# QFN32-TQFP32_v1_0.net
KiCad netlist of a schematic drawn in EAGLE
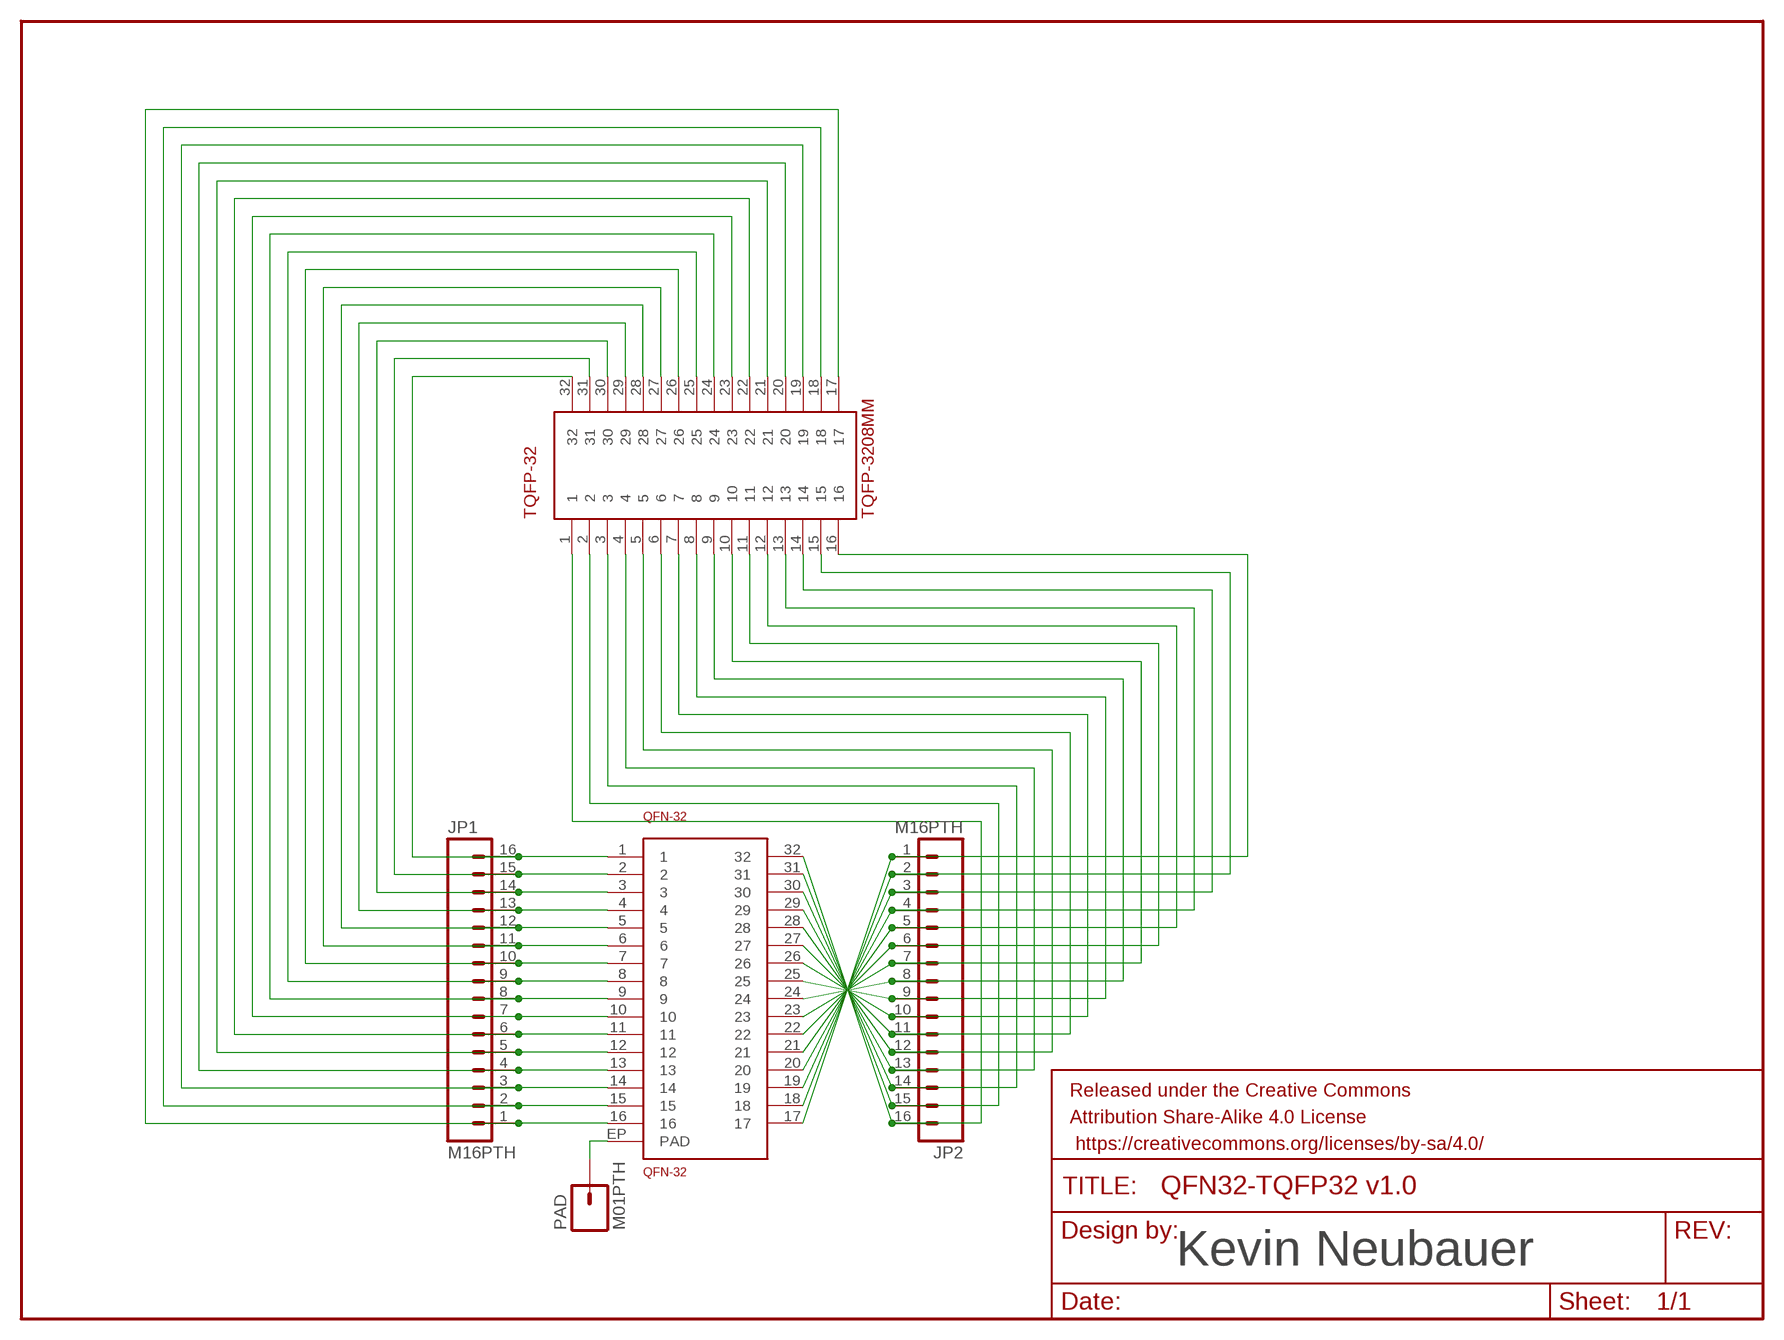
[diagram p0: schematic, sheet 1]

(export (version "E")
  (design (tool "Eeschema 10.0.6"))
  (components
    (comp (ref "FRAME1")
      (value "FRAME-LETTER")
      (footprint "eagle-import:CREATIVE_COMMONS")
      (libsource (lib "eagle-import") (part "FRAME-LETTER"))
    )
    (comp (ref "JP1")
      (value "M16PTH")
      (footprint "eagle-import:1X16")
      (libsource (lib "eagle-import") (part "M16PTH"))
    )
    (comp (ref "JP2")
      (value "M16PTH")
      (footprint "eagle-import:1X16")
      (libsource (lib "eagle-import") (part "M16PTH"))
    )
    (comp (ref "PAD")
      (value "M01PTH")
      (footprint "eagle-import:1X01")
      (libsource (lib "eagle-import") (part "M01PTH"))
    )
    (comp (ref "QFN-32")
      (value "QFN-32")
      (footprint "eagle-import:QFN-32")
      (libsource (lib "eagle-import") (part "QFN-32"))
    )
    (comp (ref "TQFP-32")
      (value "TQFP-3208MM")
      (footprint "eagle-import:TQFP32-08")
      (libsource (lib "eagle-import") (part "TQFP-3208MM"))
    )
  )
  (nets
    (net (code "1") (name "Net-(JP1-Pad1)") (class "Default")
      (node (ref "JP1") (pin "1") (pinfunction "1_1") (pintype "passive"))
      (node (ref "QFN-32") (pin "16") (pinfunction "16_16") (pintype "bidirectional"))
      (node (ref "TQFP-32") (pin "17") (pinfunction "17_17") (pintype "bidirectional"))
    )
    (net (code "2") (name "Net-(JP1-Pad2)") (class "Default")
      (node (ref "JP1") (pin "2") (pinfunction "2_2") (pintype "passive"))
      (node (ref "QFN-32") (pin "15") (pinfunction "15_15") (pintype "bidirectional"))
      (node (ref "TQFP-32") (pin "18") (pinfunction "18_18") (pintype "bidirectional"))
    )
    (net (code "3") (name "Net-(JP1-Pad3)") (class "Default")
      (node (ref "JP1") (pin "3") (pinfunction "3_3") (pintype "passive"))
      (node (ref "QFN-32") (pin "14") (pinfunction "14_14") (pintype "bidirectional"))
      (node (ref "TQFP-32") (pin "19") (pinfunction "19_19") (pintype "bidirectional"))
    )
    (net (code "4") (name "Net-(JP1-Pad4)") (class "Default")
      (node (ref "JP1") (pin "4") (pinfunction "4_4") (pintype "passive"))
      (node (ref "QFN-32") (pin "13") (pinfunction "13_13") (pintype "bidirectional"))
      (node (ref "TQFP-32") (pin "20") (pinfunction "20_20") (pintype "bidirectional"))
    )
    (net (code "5") (name "Net-(JP1-Pad5)") (class "Default")
      (node (ref "JP1") (pin "5") (pinfunction "5_5") (pintype "passive"))
      (node (ref "QFN-32") (pin "12") (pinfunction "12_12") (pintype "bidirectional"))
      (node (ref "TQFP-32") (pin "21") (pinfunction "21_21") (pintype "bidirectional"))
    )
    (net (code "6") (name "Net-(JP1-Pad6)") (class "Default")
      (node (ref "JP1") (pin "6") (pinfunction "6_6") (pintype "passive"))
      (node (ref "QFN-32") (pin "11") (pinfunction "11_11") (pintype "bidirectional"))
      (node (ref "TQFP-32") (pin "22") (pinfunction "22_22") (pintype "bidirectional"))
    )
    (net (code "7") (name "Net-(JP1-Pad7)") (class "Default")
      (node (ref "JP1") (pin "7") (pinfunction "7_7") (pintype "passive"))
      (node (ref "QFN-32") (pin "10") (pinfunction "10_10") (pintype "bidirectional"))
      (node (ref "TQFP-32") (pin "23") (pinfunction "23_23") (pintype "bidirectional"))
    )
    (net (code "8") (name "Net-(JP1-Pad8)") (class "Default")
      (node (ref "JP1") (pin "8") (pinfunction "8_8") (pintype "passive"))
      (node (ref "QFN-32") (pin "9") (pinfunction "9_9") (pintype "bidirectional"))
      (node (ref "TQFP-32") (pin "24") (pinfunction "24_24") (pintype "bidirectional"))
    )
    (net (code "9") (name "Net-(JP1-Pad9)") (class "Default")
      (node (ref "JP1") (pin "9") (pinfunction "9_9") (pintype "passive"))
      (node (ref "QFN-32") (pin "8") (pinfunction "8_8") (pintype "bidirectional"))
      (node (ref "TQFP-32") (pin "25") (pinfunction "25_25") (pintype "bidirectional"))
    )
    (net (code "10") (name "Net-(JP1-Pad10)") (class "Default")
      (node (ref "JP1") (pin "10") (pinfunction "10_10") (pintype "passive"))
      (node (ref "QFN-32") (pin "7") (pinfunction "7_7") (pintype "bidirectional"))
      (node (ref "TQFP-32") (pin "26") (pinfunction "26_26") (pintype "bidirectional"))
    )
    (net (code "11") (name "Net-(JP1-Pad11)") (class "Default")
      (node (ref "JP1") (pin "11") (pinfunction "11_11") (pintype "passive"))
      (node (ref "QFN-32") (pin "6") (pinfunction "6_6") (pintype "bidirectional"))
      (node (ref "TQFP-32") (pin "27") (pinfunction "27_27") (pintype "bidirectional"))
    )
    (net (code "12") (name "Net-(JP1-Pad12)") (class "Default")
      (node (ref "JP1") (pin "12") (pinfunction "12_12") (pintype "passive"))
      (node (ref "QFN-32") (pin "5") (pinfunction "5_5") (pintype "bidirectional"))
      (node (ref "TQFP-32") (pin "28") (pinfunction "28_28") (pintype "bidirectional"))
    )
    (net (code "13") (name "Net-(JP1-Pad13)") (class "Default")
      (node (ref "JP1") (pin "13") (pinfunction "13_13") (pintype "passive"))
      (node (ref "QFN-32") (pin "4") (pinfunction "4_4") (pintype "bidirectional"))
      (node (ref "TQFP-32") (pin "29") (pinfunction "29_29") (pintype "bidirectional"))
    )
    (net (code "14") (name "Net-(JP1-Pad14)") (class "Default")
      (node (ref "JP1") (pin "14") (pinfunction "14_14") (pintype "passive"))
      (node (ref "QFN-32") (pin "3") (pinfunction "3_3") (pintype "bidirectional"))
      (node (ref "TQFP-32") (pin "30") (pinfunction "30_30") (pintype "bidirectional"))
    )
    (net (code "15") (name "Net-(JP1-Pad15)") (class "Default")
      (node (ref "JP1") (pin "15") (pinfunction "15_15") (pintype "passive"))
      (node (ref "QFN-32") (pin "2") (pinfunction "2_2") (pintype "bidirectional"))
      (node (ref "TQFP-32") (pin "31") (pinfunction "31_31") (pintype "bidirectional"))
    )
    (net (code "16") (name "Net-(JP1-Pad16)") (class "Default")
      (node (ref "JP1") (pin "16") (pinfunction "16_16") (pintype "passive"))
      (node (ref "QFN-32") (pin "1") (pinfunction "1_1") (pintype "bidirectional"))
      (node (ref "TQFP-32") (pin "32") (pinfunction "32_32") (pintype "bidirectional"))
    )
    (net (code "17") (name "Net-(JP2-Pad1)") (class "Default")
      (node (ref "JP2") (pin "1") (pinfunction "1_1") (pintype "passive"))
      (node (ref "QFN-32") (pin "17") (pinfunction "17_17") (pintype "bidirectional"))
      (node (ref "TQFP-32") (pin "16") (pinfunction "16_16") (pintype "bidirectional"))
    )
    (net (code "18") (name "Net-(JP2-Pad2)") (class "Default")
      (node (ref "JP2") (pin "2") (pinfunction "2_2") (pintype "passive"))
      (node (ref "QFN-32") (pin "18") (pinfunction "18_18") (pintype "bidirectional"))
      (node (ref "TQFP-32") (pin "15") (pinfunction "15_15") (pintype "bidirectional"))
    )
    (net (code "19") (name "Net-(JP2-Pad3)") (class "Default")
      (node (ref "JP2") (pin "3") (pinfunction "3_3") (pintype "passive"))
      (node (ref "QFN-32") (pin "19") (pinfunction "19_19") (pintype "bidirectional"))
      (node (ref "TQFP-32") (pin "14") (pinfunction "14_14") (pintype "bidirectional"))
    )
    (net (code "20") (name "Net-(JP2-Pad4)") (class "Default")
      (node (ref "JP2") (pin "4") (pinfunction "4_4") (pintype "passive"))
      (node (ref "QFN-32") (pin "20") (pinfunction "20_20") (pintype "bidirectional"))
      (node (ref "TQFP-32") (pin "13") (pinfunction "13_13") (pintype "bidirectional"))
    )
    (net (code "21") (name "Net-(JP2-Pad5)") (class "Default")
      (node (ref "JP2") (pin "5") (pinfunction "5_5") (pintype "passive"))
      (node (ref "QFN-32") (pin "21") (pinfunction "21_21") (pintype "bidirectional"))
      (node (ref "TQFP-32") (pin "12") (pinfunction "12_12") (pintype "bidirectional"))
    )
    (net (code "22") (name "Net-(JP2-Pad6)") (class "Default")
      (node (ref "JP2") (pin "6") (pinfunction "6_6") (pintype "passive"))
      (node (ref "QFN-32") (pin "22") (pinfunction "22_22") (pintype "bidirectional"))
      (node (ref "TQFP-32") (pin "11") (pinfunction "11_11") (pintype "bidirectional"))
    )
    (net (code "23") (name "Net-(JP2-Pad7)") (class "Default")
      (node (ref "JP2") (pin "7") (pinfunction "7_7") (pintype "passive"))
      (node (ref "QFN-32") (pin "23") (pinfunction "23_23") (pintype "bidirectional"))
      (node (ref "TQFP-32") (pin "10") (pinfunction "10_10") (pintype "bidirectional"))
    )
    (net (code "24") (name "Net-(JP2-Pad8)") (class "Default")
      (node (ref "JP2") (pin "8") (pinfunction "8_8") (pintype "passive"))
      (node (ref "QFN-32") (pin "24") (pinfunction "24_24") (pintype "bidirectional"))
      (node (ref "TQFP-32") (pin "9") (pinfunction "9_9") (pintype "bidirectional"))
    )
    (net (code "25") (name "Net-(JP2-Pad9)") (class "Default")
      (node (ref "JP2") (pin "9") (pinfunction "9_9") (pintype "passive"))
      (node (ref "QFN-32") (pin "25") (pinfunction "25_25") (pintype "bidirectional"))
      (node (ref "TQFP-32") (pin "8") (pinfunction "8_8") (pintype "bidirectional"))
    )
    (net (code "26") (name "Net-(JP2-Pad10)") (class "Default")
      (node (ref "JP2") (pin "10") (pinfunction "10_10") (pintype "passive"))
      (node (ref "QFN-32") (pin "26") (pinfunction "26_26") (pintype "bidirectional"))
      (node (ref "TQFP-32") (pin "7") (pinfunction "7_7") (pintype "bidirectional"))
    )
    (net (code "27") (name "Net-(JP2-Pad11)") (class "Default")
      (node (ref "JP2") (pin "11") (pinfunction "11_11") (pintype "passive"))
      (node (ref "QFN-32") (pin "27") (pinfunction "27_27") (pintype "bidirectional"))
      (node (ref "TQFP-32") (pin "6") (pinfunction "6_6") (pintype "bidirectional"))
    )
    (net (code "28") (name "Net-(JP2-Pad12)") (class "Default")
      (node (ref "JP2") (pin "12") (pinfunction "12_12") (pintype "passive"))
      (node (ref "QFN-32") (pin "28") (pinfunction "28_28") (pintype "bidirectional"))
      (node (ref "TQFP-32") (pin "5") (pinfunction "5_5") (pintype "bidirectional"))
    )
    (net (code "29") (name "Net-(JP2-Pad13)") (class "Default")
      (node (ref "JP2") (pin "13") (pinfunction "13_13") (pintype "passive"))
      (node (ref "QFN-32") (pin "29") (pinfunction "29_29") (pintype "bidirectional"))
      (node (ref "TQFP-32") (pin "4") (pinfunction "4_4") (pintype "bidirectional"))
    )
    (net (code "30") (name "Net-(JP2-Pad14)") (class "Default")
      (node (ref "JP2") (pin "14") (pinfunction "14_14") (pintype "passive"))
      (node (ref "QFN-32") (pin "30") (pinfunction "30_30") (pintype "bidirectional"))
      (node (ref "TQFP-32") (pin "3") (pinfunction "3_3") (pintype "bidirectional"))
    )
    (net (code "31") (name "Net-(JP2-Pad15)") (class "Default")
      (node (ref "JP2") (pin "15") (pinfunction "15_15") (pintype "passive"))
      (node (ref "QFN-32") (pin "31") (pinfunction "31_31") (pintype "bidirectional"))
      (node (ref "TQFP-32") (pin "2") (pinfunction "2_2") (pintype "bidirectional"))
    )
    (net (code "32") (name "Net-(JP2-Pad16)") (class "Default")
      (node (ref "JP2") (pin "16") (pinfunction "16_16") (pintype "passive"))
      (node (ref "QFN-32") (pin "32") (pinfunction "32_32") (pintype "bidirectional"))
      (node (ref "TQFP-32") (pin "1") (pinfunction "1_1") (pintype "bidirectional"))
    )
    (net (code "33") (name "Net-(QFN-32-PAD)") (class "Default")
      (node (ref "PAD") (pin "1") (pinfunction "1_1") (pintype "passive"))
      (node (ref "QFN-32") (pin "EP") (pinfunction "PAD_EP") (pintype "bidirectional"))
    )
  )
)
